# Power.net
KiCad netlist of a schematic drawn in Altium Designer
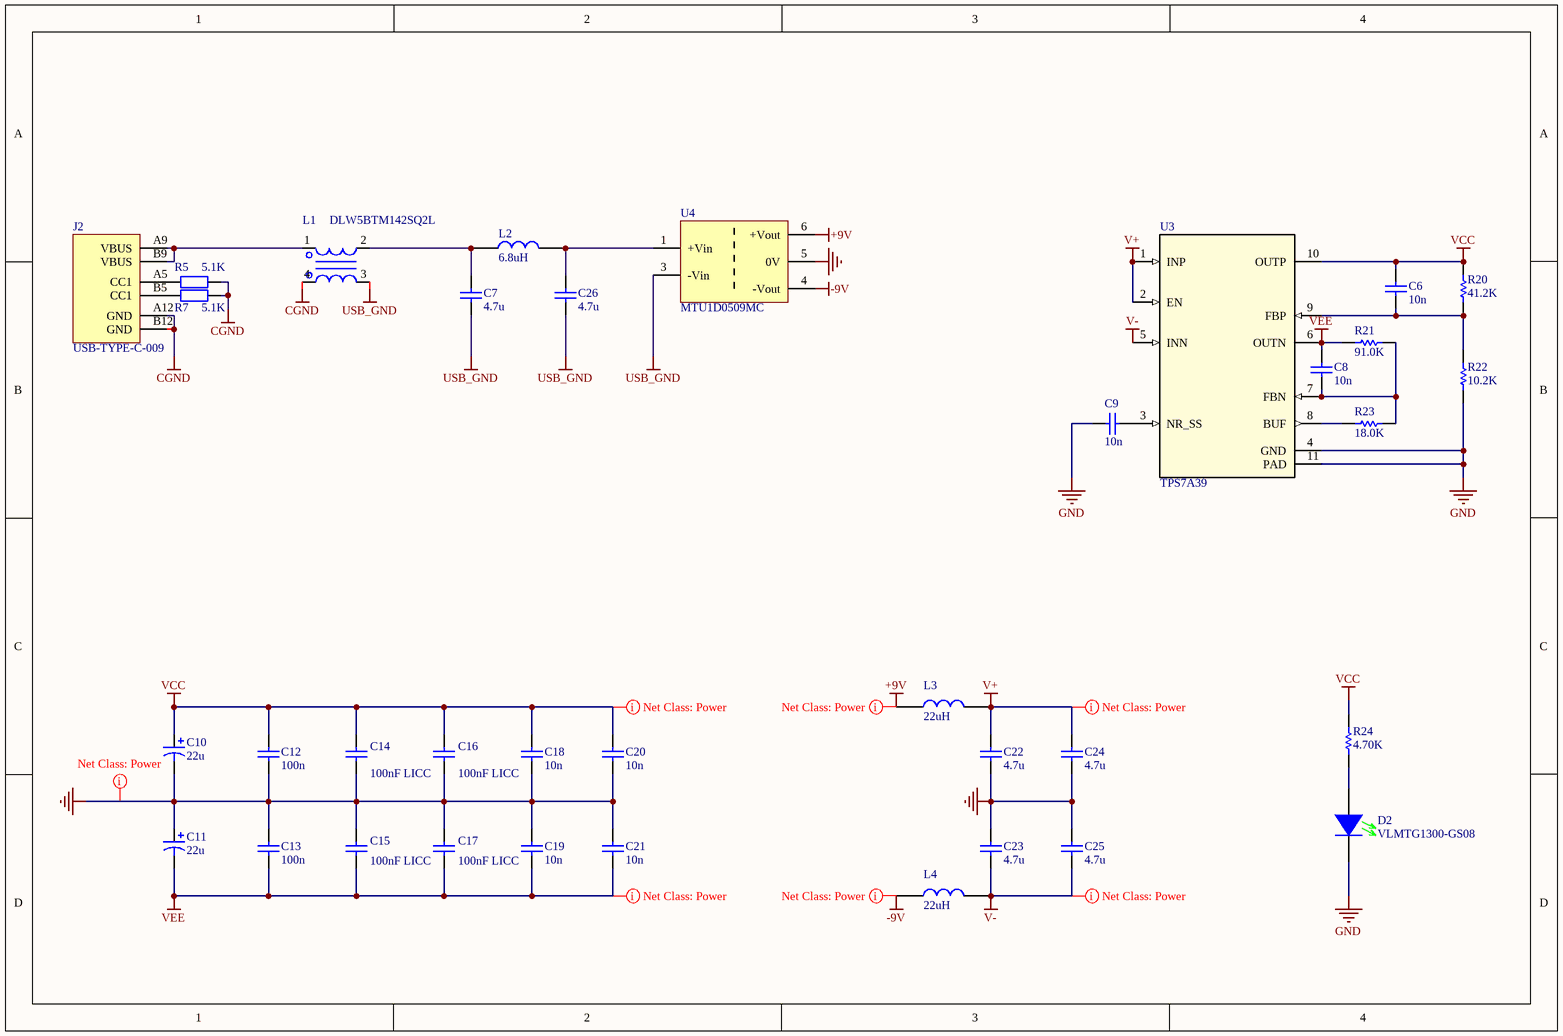
[diagram p0: Power.SchDoc]

(export (version "E")
  (design (tool "Eeschema 10.0.6"))
  (components
    (comp (ref "C6")
      (value "10n")
      (footprint "CAPC0402(1005)50_M")
      (description "CAP CER 10NF±5% 25V C0G 0402")
      (fields
        (field (name "MANUFACTURER") "Murata")
        (field (name "MANUFACTURER PART NUMBER") "GRM1555C1E103JE01D")
      )
      (libsource (lib "Murata GRM 0402") (part "Capacitor_Generic"))
    )
    (comp (ref "C7")
      (value "4.7u")
      (footprint "CAPC0805(2012)100_M")
      (description "CAP CER 4.7UF 50V X7R 0805")
      (fields
        (field (name "MANUFACTURER") "Murata")
        (field (name "MANUFACTURER PART NUMBER") "GRM21BZ71H475KE15K")
      )
      (libsource (lib "0805 Caps") (part "GRM21BZ71H475KE15K"))
    )
    (comp (ref "C8")
      (value "10n")
      (footprint "CAPC0402(1005)50_M")
      (description "CAP CER 10NF±5% 25V C0G 0402")
      (fields
        (field (name "MANUFACTURER") "Murata")
        (field (name "MANUFACTURER PART NUMBER") "GRM1555C1E103JE01D")
      )
      (libsource (lib "Murata GRM 0402") (part "Capacitor_Generic"))
    )
    (comp (ref "C9")
      (value "10n")
      (footprint "CAPC0402(1005)50_M")
      (description "CAP CER 10NF±5% 25V C0G 0402")
      (fields
        (field (name "MANUFACTURER") "Murata")
        (field (name "MANUFACTURER PART NUMBER") "GRM1555C1E103JE01D")
      )
      (libsource (lib "Murata GRM 0402") (part "Capacitor_Generic"))
    )
    (comp (ref "C10")
      (value "22u")
      (footprint "KEMET B_M")
      (description "CAP TANT 22UF 10% 16V 1411")
      (fields
        (field (name "MANUFACTURER") "KEMET")
        (field (name "MANUFACTURER PART NUMBER") "T491B226K016AT")
      )
      (libsource (lib "Misc Caps") (part "T491B226K016AT"))
    )
    (comp (ref "C11")
      (value "22u")
      (footprint "KEMET B_M")
      (description "CAP TANT 22UF 10% 16V 1411")
      (fields
        (field (name "MANUFACTURER") "KEMET")
        (field (name "MANUFACTURER PART NUMBER") "T491B226K016AT")
      )
      (libsource (lib "Misc Caps") (part "T491B226K016AT"))
    )
    (comp (ref "C12")
      (value "100n")
      (footprint "CAPC0603(1608)100_M")
      (description "CAPACITOR CERAMIC, 0.1UF, 50V, X7R, 10%, 0603")
      (fields
        (field (name "MANUFACTURER") "Yageo")
        (field (name "MANUFACTURER PART NUMBER") "CC0603KRX7R9BB104")
      )
      (libsource (lib "0603 Caps") (part "CC0603KRX7R9BB104"))
    )
    (comp (ref "C13")
      (value "100n")
      (footprint "CAPC0603(1608)100_M")
      (description "CAPACITOR CERAMIC, 0.1UF, 50V, X7R, 10%, 0603")
      (fields
        (field (name "MANUFACTURER") "Yageo")
        (field (name "MANUFACTURER PART NUMBER") "CC0603KRX7R9BB104")
      )
      (libsource (lib "0603 Caps") (part "CC0603KRX7R9BB104"))
    )
    (comp (ref "C14")
      (value "100nF LICC")
      (footprint "CAPC0306_M")
      (description "CAP CER 0.1UF 25V X7R 0306")
      (fields (field (name "MANUFACTURER") "YAGEO") (field (name "Comment") "100n LICC"))
      (libsource (lib "Misc Caps") (part "TWK107B7104MVHT"))
    )
    (comp (ref "C15")
      (value "100nF LICC")
      (footprint "CAPC0306_M")
      (description "CAP CER 0.1UF 25V X7R 0306")
      (fields (field (name "MANUFACTURER") "YAGEO") (field (name "Comment") "100n LICC"))
      (libsource (lib "Misc Caps") (part "TWK107B7104MVHT"))
    )
    (comp (ref "C16")
      (value "100nF LICC")
      (footprint "CAPC0306_M")
      (description "CAP CER 0.1UF 25V X7R 0306")
      (fields (field (name "MANUFACTURER") "YAGEO") (field (name "Comment") "100n LICC"))
      (libsource (lib "Misc Caps") (part "TWK107B7104MVHT"))
    )
    (comp (ref "C17")
      (value "100nF LICC")
      (footprint "CAPC0306_M")
      (description "CAP CER 0.1UF 25V X7R 0306")
      (fields (field (name "MANUFACTURER") "YAGEO") (field (name "Comment") "100n LICC"))
      (libsource (lib "Misc Caps") (part "TWK107B7104MVHT"))
    )
    (comp (ref "C18")
      (value "10n")
      (footprint "CAPC0402(1005)50_M")
      (description "CAP CER 10NF±10% 50V X7R 0402")
      (fields (field (name "PART NUMBER") "GRM155R71H103KA88") (field (name "TOLERANCE") "±10%"))
      (libsource (lib "Murata GRM 0402") (part "Capacitor_Generic"))
    )
    (comp (ref "C19")
      (value "10n")
      (footprint "CAPC0402(1005)50_M")
      (description "CAP CER 10NF±10% 50V X7R 0402")
      (fields (field (name "PART NUMBER") "GRM155R71H103KA88") (field (name "TOLERANCE") "±10%"))
      (libsource (lib "Murata GRM 0402") (part "Capacitor_Generic"))
    )
    (comp (ref "C20")
      (value "10n")
      (footprint "CAPC0402(1005)50_M")
      (description "CAP CER 10NF±10% 50V X7R 0402")
      (fields (field (name "PART NUMBER") "GRM155R71H103KA88") (field (name "TOLERANCE") "±10%"))
      (libsource (lib "Murata GRM 0402") (part "Capacitor_Generic"))
    )
    (comp (ref "C21")
      (value "10n")
      (footprint "CAPC0402(1005)50_M")
      (description "CAP CER 10NF±10% 50V X7R 0402")
      (fields (field (name "PART NUMBER") "GRM155R71H103KA88") (field (name "TOLERANCE") "±10%"))
      (libsource (lib "Murata GRM 0402") (part "Capacitor_Generic"))
    )
    (comp (ref "C22")
      (value "4.7u")
      (footprint "CAPC0805(2012)100_M")
      (description "CAP CER 4.7UF 50V X7R 0805")
      (fields
        (field (name "MANUFACTURER") "Murata")
        (field (name "MANUFACTURER PART NUMBER") "GRM21BZ71H475KE15K")
      )
      (libsource (lib "0805 Caps") (part "GRM21BZ71H475KE15K"))
    )
    (comp (ref "C23")
      (value "4.7u")
      (footprint "CAPC0805(2012)100_M")
      (description "CAP CER 4.7UF 50V X7R 0805")
      (fields
        (field (name "MANUFACTURER") "Murata")
        (field (name "MANUFACTURER PART NUMBER") "GRM21BZ71H475KE15K")
      )
      (libsource (lib "0805 Caps") (part "GRM21BZ71H475KE15K"))
    )
    (comp (ref "C24")
      (value "4.7u")
      (footprint "CAPC0805(2012)100_M")
      (description "CAP CER 4.7UF 50V X7R 0805")
      (fields
        (field (name "MANUFACTURER") "Murata")
        (field (name "MANUFACTURER PART NUMBER") "GRM21BZ71H475KE15K")
      )
      (libsource (lib "0805 Caps") (part "GRM21BZ71H475KE15K"))
    )
    (comp (ref "C25")
      (value "4.7u")
      (footprint "CAPC0805(2012)100_M")
      (description "CAP CER 4.7UF 50V X7R 0805")
      (fields
        (field (name "MANUFACTURER") "Murata")
        (field (name "MANUFACTURER PART NUMBER") "GRM21BZ71H475KE15K")
      )
      (libsource (lib "0805 Caps") (part "GRM21BZ71H475KE15K"))
    )
    (comp (ref "C26")
      (value "4.7u")
      (footprint "CAPC0805(2012)100_M")
      (description "CAP CER 4.7UF 50V X7R 0805")
      (fields
        (field (name "MANUFACTURER") "Murata")
        (field (name "MANUFACTURER PART NUMBER") "GRM21BZ71H475KE15K")
      )
      (libsource (lib "0805 Caps") (part "GRM21BZ71H475KE15K"))
    )
    (comp (ref "D2")
      (value "VLMTG1300-GS08")
      (footprint "LED0603(1608)_M")
      (description "LED GREEN 0603 SMD")
      (fields (field (name "MANUFACTURER") "Vishay Semiconductors"))
      (libsource (lib "Discretes") (part "VLMTG1300-GS08"))
    )
    (comp (ref "J2")
      (value "USB-TYPE-C-009")
      (footprint "GCT_USB4125-GF-A_REVA2")
      (description "USB Type C 3.1 connector")
      (fields (field (name "MANUFACTURER") "DEALON") (field (name "Comment") "USB- C"))
      (libsource (lib "rogowski-relief") (part "USB- C"))
    )
    (comp (ref "L1")
      (value "DLW5BTM142SQ2L")
      (footprint "SDCW3225")
      (description "Common Mode Choke Coils")
      (fields (field (name "MANUFACTURER") "Murata") (field (name "Comment") "Choke"))
      (libsource (lib "rogowski-relief") (part "Choke"))
    )
    (comp (ref "L2")
      (value "6.8uH")
      (footprint "SML-1210")
      (description "Inductor")
      (fields (field (name "MANUFACTURER") "TDK"))
      (libsource (lib "rogowski-relief") (part "Inductor"))
    )
    (comp (ref "L3")
      (value "22uH")
      (footprint "SML-1210")
      (description "Inductor")
      (fields (field (name "MANUFACTURER") "TDK"))
      (libsource (lib "rogowski-relief") (part "Inductor"))
    )
    (comp (ref "L4")
      (value "22uH")
      (footprint "SML-1210")
      (description "Inductor")
      (fields (field (name "MANUFACTURER") "TDK"))
      (libsource (lib "rogowski-relief") (part "Inductor"))
    )
    (comp (ref "R5")
      (value "5.1K")
      (footprint "SMR-0402")
      (description "Resistor")
      (fields (field (name "MANUFACTURER") "YAGEO") (field (name "Comment") "Res"))
      (libsource (lib "rogowski-relief") (part "Res"))
    )
    (comp (ref "R7")
      (value "5.1K")
      (footprint "SMR-0402")
      (description "Resistor")
      (fields (field (name "MANUFACTURER") "YAGEO") (field (name "Comment") "Res"))
      (libsource (lib "rogowski-relief") (part "Res"))
    )
    (comp (ref "R20")
      (value "41.2K")
      (footprint "RESC0402(1005)_M")
      (description "RES 41.2K OHM 1% 1/16W 0402")
      (fields (field (name "PART NUMBER") "RESC0402-41K2-1pct"))
      (libsource (lib "R0402 - 1pct") (part "Resistor_Generic"))
    )
    (comp (ref "R21")
      (value "91.0K")
      (footprint "RESC0402(1005)_M")
      (description "RES 91.0K OHM 1% 1/16W 0402")
      (fields (field (name "PART NUMBER") "RESC0402-91K0-1pct"))
      (libsource (lib "R0402 - 1pct") (part "Resistor_Generic"))
    )
    (comp (ref "R22")
      (value "10.2K")
      (footprint "RESC0402(1005)_M")
      (description "RES 10.2K OHM 1% 1/16W 0402")
      (fields (field (name "PART NUMBER") "RESC0402-10K2-1pct"))
      (libsource (lib "R0402 - 1pct") (part "Resistor_Generic"))
    )
    (comp (ref "R23")
      (value "18.0K")
      (footprint "RESC0402(1005)_M")
      (description "RES 18.0K OHM 1% 1/16W 0402")
      (fields (field (name "PART NUMBER") "RESC0402-18K0-1pct"))
      (libsource (lib "R0402 - 1pct") (part "Resistor_Generic"))
    )
    (comp (ref "R24")
      (value "4.70K")
      (footprint "RESC0603(1608)_M")
      (description "RES 4.70K OHM 1% 1/10W 0603")
      (fields (field (name "PART NUMBER") "RESC0603-4K70-1pct"))
      (libsource (lib "R0603 - 1pct") (part "Resistor_Generic"))
    )
    (comp (ref "U3")
      (value "TPS7A39")
      (footprint "DSC0010J_NV")
      (description "IC REG LINEAR POS/NEG ADJ 10WSON")
      (fields
        (field (name "MANUFACTURER_PART_NUMBER") "TPS7A3901DSCR")
        (field (name "MANUFACTURER") "Texas Instruments")
        (field (name "COPYRIGHT") "Copyright (C) 2022 Ultra Librarian. All rights reserved.")
      )
      (libsource (lib "IC") (part "TPS7A3901DSCR"))
    )
    (comp (ref "U4")
      (value "MTU1D0509MC")
      (footprint "MTU1D0509MC")
      (description "Isolated DC/DC 1W 5-> +/-9V")
      (fields (field (name "MANUFACTURER") "Murata"))
      (libsource (lib "probe") (part "MTU1D0509MC"))
    )
  )
  (nets
    (net (code "1") (name "+9V") (class "Default")
      (node (ref "L3") (pin "1") (pinfunction "1_1") (pintype "passive"))
      (node (ref "U4") (pin "6") (pinfunction "+Vout_6") (pintype "power_in"))
    )
    (net (code "2") (name "-9V") (class "Default")
      (node (ref "L4") (pin "1") (pinfunction "1_1") (pintype "passive"))
      (node (ref "U4") (pin "4") (pinfunction "-Vout_4") (pintype "power_in"))
    )
    (net (code "3") (name "CGND") (class "Default")
      (node (ref "J2") (pin "A12") (pinfunction "GND_A12") (pintype "power_in"))
      (node (ref "J2") (pin "B12") (pinfunction "GND_B12") (pintype "power_in"))
      (node (ref "L1") (pin "4") (pinfunction "4_4") (pintype "passive"))
      (node (ref "R5") (pin "1") (pinfunction "1_1") (pintype "passive"))
      (node (ref "R7") (pin "1") (pinfunction "1_1") (pintype "passive"))
    )
    (net (code "4") (name "GND") (class "Default")
      (node (ref "C10") (pin "2") (pinfunction "2_2") (pintype "passive"))
      (node (ref "C11") (pin "1") (pinfunction "1_1") (pintype "passive"))
      (node (ref "C12") (pin "2") (pinfunction "2_2") (pintype "passive"))
      (node (ref "C13") (pin "1") (pinfunction "1_1") (pintype "passive"))
      (node (ref "C14") (pin "2") (pinfunction "2_2") (pintype "passive"))
      (node (ref "C15") (pin "1") (pinfunction "1_1") (pintype "passive"))
      (node (ref "C16") (pin "2") (pinfunction "2_2") (pintype "passive"))
      (node (ref "C17") (pin "1") (pinfunction "1_1") (pintype "passive"))
      (node (ref "C18") (pin "2") (pinfunction "2_2") (pintype "passive"))
      (node (ref "C19") (pin "1") (pinfunction "1_1") (pintype "passive"))
      (node (ref "C20") (pin "2") (pinfunction "2_2") (pintype "passive"))
      (node (ref "C21") (pin "1") (pinfunction "1_1") (pintype "passive"))
      (node (ref "C22") (pin "2") (pinfunction "2_2") (pintype "passive"))
      (node (ref "C23") (pin "1") (pinfunction "1_1") (pintype "passive"))
      (node (ref "C24") (pin "2") (pinfunction "2_2") (pintype "passive"))
      (node (ref "C25") (pin "2") (pinfunction "2_2") (pintype "passive"))
      (node (ref "C9") (pin "2") (pinfunction "2_2") (pintype "passive"))
      (node (ref "D2") (pin "2") (pinfunction "K_2") (pintype "passive"))
      (node (ref "R22") (pin "2") (pinfunction "2_2") (pintype "passive"))
      (node (ref "U3") (pin "11") (pinfunction "PAD_11") (pintype "power_in"))
      (node (ref "U3") (pin "4") (pinfunction "GND_4") (pintype "power_in"))
      (node (ref "U4") (pin "5") (pinfunction "0V_5") (pintype "power_in"))
    )
    (net (code "5") (name "Net-(C7-Pad1)") (class "Default")
      (node (ref "C7") (pin "1") (pinfunction "1_1") (pintype "passive"))
      (node (ref "L1") (pin "2") (pinfunction "2_2") (pintype "passive"))
      (node (ref "L2") (pin "1") (pinfunction "1_1") (pintype "passive"))
    )
    (net (code "6") (name "Net-(D2-A)") (class "Default")
      (node (ref "D2") (pin "1") (pinfunction "A_1") (pintype "passive"))
      (node (ref "R24") (pin "2") (pinfunction "2_2") (pintype "passive"))
    )
    (net (code "7") (name "Net-(J2-CC1-PadA5)") (class "Default")
      (node (ref "J2") (pin "A5") (pinfunction "CC1_A5") (pintype "power_in"))
      (node (ref "R5") (pin "2") (pinfunction "2_2") (pintype "passive"))
    )
    (net (code "8") (name "Net-(J2-CC1-PadB5)") (class "Default")
      (node (ref "J2") (pin "B5") (pinfunction "CC1_B5") (pintype "power_in"))
      (node (ref "R7") (pin "2") (pinfunction "2_2") (pintype "passive"))
    )
    (net (code "9") (name "Net-(J2-VBUS-PadA9)") (class "Default")
      (node (ref "J2") (pin "A9") (pinfunction "VBUS_A9") (pintype "power_in"))
      (node (ref "J2") (pin "B9") (pinfunction "VBUS_B9") (pintype "power_in"))
      (node (ref "L1") (pin "1") (pinfunction "1_1") (pintype "passive"))
    )
    (net (code "10") (name "Net-(U3-BUF)") (class "Default")
      (node (ref "R23") (pin "2") (pinfunction "2_2") (pintype "passive"))
      (node (ref "U3") (pin "8") (pinfunction "BUF_8") (pintype "output"))
    )
    (net (code "11") (name "Net-(U3-FBN)") (class "Default")
      (node (ref "C8") (pin "1") (pinfunction "1_1") (pintype "passive"))
      (node (ref "R21") (pin "1") (pinfunction "1_1") (pintype "passive"))
      (node (ref "R23") (pin "1") (pinfunction "1_1") (pintype "passive"))
      (node (ref "U3") (pin "7") (pinfunction "FBN_7") (pintype "input"))
    )
    (net (code "12") (name "Net-(U3-FBP)") (class "Default")
      (node (ref "C6") (pin "1") (pinfunction "1_1") (pintype "passive"))
      (node (ref "R20") (pin "2") (pinfunction "2_2") (pintype "passive"))
      (node (ref "R22") (pin "1") (pinfunction "1_1") (pintype "passive"))
      (node (ref "U3") (pin "9") (pinfunction "FBP_9") (pintype "input"))
    )
    (net (code "13") (name "Net-(U3-NR_SS)") (class "Default")
      (node (ref "C9") (pin "1") (pinfunction "1_1") (pintype "passive"))
      (node (ref "U3") (pin "3") (pinfunction "NR_SS_3") (pintype "input"))
    )
    (net (code "14") (name "Net-(U4-+Vin)") (class "Default")
      (node (ref "C26") (pin "1") (pinfunction "1_1") (pintype "passive"))
      (node (ref "L2") (pin "2") (pinfunction "2_2") (pintype "passive"))
      (node (ref "U4") (pin "1") (pinfunction "+Vin_1") (pintype "power_in"))
    )
    (net (code "15") (name "USB_GND") (class "Default")
      (node (ref "C26") (pin "2") (pinfunction "2_2") (pintype "passive"))
      (node (ref "C7") (pin "2") (pinfunction "2_2") (pintype "passive"))
      (node (ref "L1") (pin "3") (pinfunction "3_3") (pintype "passive"))
      (node (ref "U4") (pin "3") (pinfunction "-Vin_3") (pintype "power_in"))
    )
    (net (code "16") (name "V+") (class "Default")
      (node (ref "C22") (pin "1") (pinfunction "1_1") (pintype "passive"))
      (node (ref "C24") (pin "1") (pinfunction "1_1") (pintype "passive"))
      (node (ref "L3") (pin "2") (pinfunction "2_2") (pintype "passive"))
      (node (ref "U3") (pin "1") (pinfunction "INP_1") (pintype "input"))
      (node (ref "U3") (pin "2") (pinfunction "EN_2") (pintype "input"))
    )
    (net (code "17") (name "V-") (class "Default")
      (node (ref "C23") (pin "2") (pinfunction "2_2") (pintype "passive"))
      (node (ref "C25") (pin "1") (pinfunction "1_1") (pintype "passive"))
      (node (ref "L4") (pin "2") (pinfunction "2_2") (pintype "passive"))
      (node (ref "U3") (pin "5") (pinfunction "INN_5") (pintype "input"))
    )
    (net (code "18") (name "VCC") (class "Default")
      (node (ref "C10") (pin "1") (pinfunction "1_1") (pintype "passive"))
      (node (ref "C12") (pin "1") (pinfunction "1_1") (pintype "passive"))
      (node (ref "C14") (pin "1") (pinfunction "1_1") (pintype "passive"))
      (node (ref "C16") (pin "1") (pinfunction "1_1") (pintype "passive"))
      (node (ref "C18") (pin "1") (pinfunction "1_1") (pintype "passive"))
      (node (ref "C20") (pin "1") (pinfunction "1_1") (pintype "passive"))
      (node (ref "C6") (pin "2") (pinfunction "2_2") (pintype "passive"))
      (node (ref "R20") (pin "1") (pinfunction "1_1") (pintype "passive"))
      (node (ref "R24") (pin "1") (pinfunction "1_1") (pintype "passive"))
      (node (ref "U3") (pin "10") (pinfunction "OUTP_10") (pintype "power_in"))
    )
    (net (code "19") (name "VEE") (class "Default")
      (node (ref "C11") (pin "2") (pinfunction "2_2") (pintype "passive"))
      (node (ref "C13") (pin "2") (pinfunction "2_2") (pintype "passive"))
      (node (ref "C15") (pin "2") (pinfunction "2_2") (pintype "passive"))
      (node (ref "C17") (pin "2") (pinfunction "2_2") (pintype "passive"))
      (node (ref "C19") (pin "2") (pinfunction "2_2") (pintype "passive"))
      (node (ref "C21") (pin "2") (pinfunction "2_2") (pintype "passive"))
      (node (ref "C8") (pin "2") (pinfunction "2_2") (pintype "passive"))
      (node (ref "R21") (pin "2") (pinfunction "2_2") (pintype "passive"))
      (node (ref "U3") (pin "6") (pinfunction "OUTN_6") (pintype "power_in"))
    )
  )
)
